# ACTUATOR_PWR_PROT.net
KiCad netlist of a schematic drawn in Altium Designer
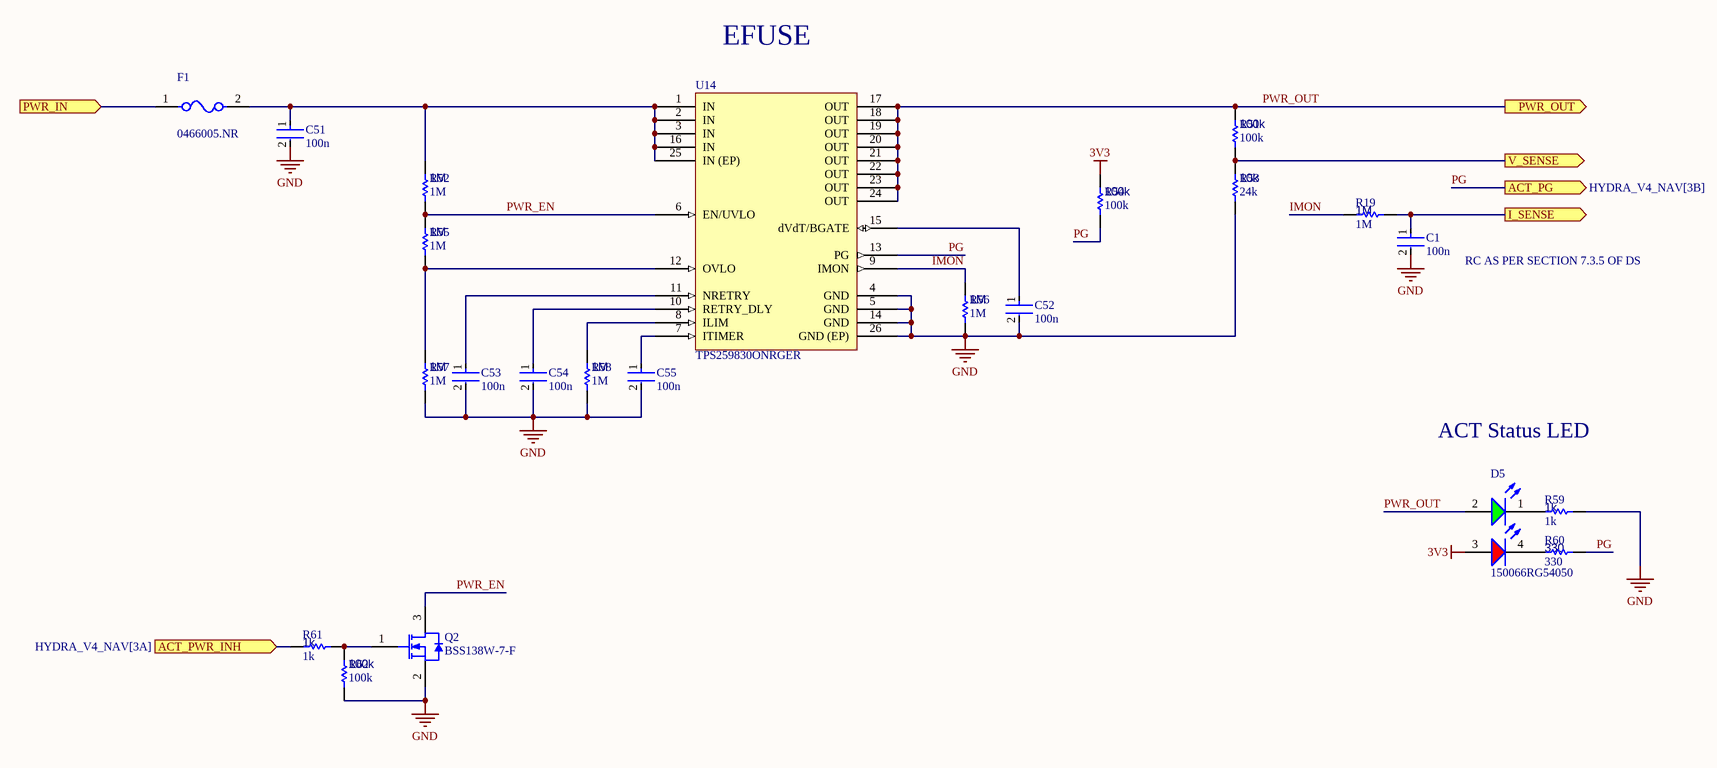
[diagram p0: ACTUATOR_PWR_PROT.SchDoc]

(export (version "E")
  (design (tool "Eeschema 10.0.6"))
  (components
    (comp (ref "C1")
      (value "100n")
      (footprint "FP-0402-L_1_0_0_05-W_0_5-IPC_A")
      (description "LARGE PADS, 0402 CAP, CHANGE COMMENT TO MATCH REAL P/N")
      (libsource (lib "Space Concordia") (part "b4654b650e69147ec39a6b967a45e02"))
    )
    (comp (ref "C51")
      (value "100n")
      (footprint "FP-0402-L_1_0_0_05-W_0_5-IPC_A")
      (description "LARGE PADS, 0402 CAP, CHANGE COMMENT TO MATCH REAL P/N")
      (libsource (lib "Space Concordia") (part "b4654b650e69147ec39a6b967a45e02"))
    )
    (comp (ref "C52")
      (value "100n")
      (footprint "FP-0402-L_1_0_0_05-W_0_5-IPC_A")
      (description "LARGE PADS, 0402 CAP, CHANGE COMMENT TO MATCH REAL P/N")
      (libsource (lib "Space Concordia") (part "b4654b650e69147ec39a6b967a45e02"))
    )
    (comp (ref "C53")
      (value "100n")
      (footprint "FP-0402-L_1_0_0_05-W_0_5-IPC_A")
      (description "LARGE PADS, 0402 CAP, CHANGE COMMENT TO MATCH REAL P/N")
      (libsource (lib "Space Concordia") (part "b4654b650e69147ec39a6b967a45e02"))
    )
    (comp (ref "C54")
      (value "100n")
      (footprint "FP-0402-L_1_0_0_05-W_0_5-IPC_A")
      (description "LARGE PADS, 0402 CAP, CHANGE COMMENT TO MATCH REAL P/N")
      (libsource (lib "Space Concordia") (part "b4654b650e69147ec39a6b967a45e02"))
    )
    (comp (ref "C55")
      (value "100n")
      (footprint "FP-0402-L_1_0_0_05-W_0_5-IPC_A")
      (description "LARGE PADS, 0402 CAP, CHANGE COMMENT TO MATCH REAL P/N")
      (libsource (lib "Space Concordia") (part "b4654b650e69147ec39a6b967a45e02"))
    )
    (comp (ref "D5")
      (value "150066RG54050")
      (footprint "WL-SBCD_0606")
      (description "Led, Red/Grn, 180Mcd/230Mcd, 624Nm/525Nm Rohs Compliant: Yes")
      (fields (field (name "SOURCE") "rgled.SchLib"))
      (libsource (lib "Space Concordia") (part "CMP-004-00034-2"))
    )
    (comp (ref "F1")
      (value "0466005.NR")
      (footprint "FP-0466-MFG")
      (description "FUSE BOARD MNT 5A 32VAC/VDC 1206")
      (fields
        (field (name "OCTOPART") "https://octopart.com/0466005.nr-littelfuse-143206")
        (field (name "MANUFACTURER") "Littelfuse Inc")
      )
      (libsource (lib "Altium Content Vault") (part "5bcf9b9f640e542cf0359d10258e979"))
    )
    (comp (ref "Q2")
      (value "BSS138W-7-F")
      (footprint "DIOD-SOT323-3_V")
      (fields (field (name "MANUFACTURER") "DiodesIncorporated"))
      (libsource (lib "Altium Content Vault") (part "NEMOS-GSD-3"))
    )
    (comp (ref "R19")
      (value "1M")
      (footprint "R0603B")
      (description "Resistor")
      (fields (field (name "ALTIUM_VALUE") "1M"))
      (libsource (lib "Space Concordia") (part "Resistor"))
    )
    (comp (ref "R51")
      (value "100k")
      (footprint "R0603B")
      (description "Resistor")
      (fields (field (name "ALTIUM_VALUE") "100k"))
      (libsource (lib "Space Concordia") (part "Resistor"))
    )
    (comp (ref "R52")
      (value "1M")
      (footprint "R0603B")
      (description "Resistor")
      (fields (field (name "ALTIUM_VALUE") "1M"))
      (libsource (lib "Space Concordia") (part "Resistor"))
    )
    (comp (ref "R53")
      (value "24k")
      (footprint "R0603B")
      (description "Resistor")
      (fields (field (name "ALTIUM_VALUE") "10k"))
      (libsource (lib "Space Concordia") (part "Resistor"))
    )
    (comp (ref "R54")
      (value "100k")
      (footprint "R0603B")
      (description "Resistor")
      (fields (field (name "ALTIUM_VALUE") "100k"))
      (libsource (lib "Space Concordia") (part "Resistor"))
    )
    (comp (ref "R55")
      (value "1M")
      (footprint "R0603B")
      (description "Resistor")
      (fields (field (name "ALTIUM_VALUE") "1M"))
      (libsource (lib "Space Concordia") (part "Resistor"))
    )
    (comp (ref "R56")
      (value "1M")
      (footprint "R0603B")
      (description "Resistor")
      (fields (field (name "ALTIUM_VALUE") "1M"))
      (libsource (lib "Space Concordia") (part "Resistor"))
    )
    (comp (ref "R57")
      (value "1M")
      (footprint "R0603B")
      (description "Resistor")
      (fields (field (name "ALTIUM_VALUE") "1M"))
      (libsource (lib "Space Concordia") (part "Resistor"))
    )
    (comp (ref "R58")
      (value "1M")
      (footprint "R0603B")
      (description "Resistor")
      (fields (field (name "ALTIUM_VALUE") "1M"))
      (libsource (lib "Space Concordia") (part "Resistor"))
    )
    (comp (ref "R59")
      (value "1k")
      (footprint "R0603B")
      (description "Resistor")
      (fields (field (name "ALTIUM_VALUE") "1k"))
      (libsource (lib "Space Concordia") (part "Resistor"))
    )
    (comp (ref "R60")
      (value "330")
      (footprint "R0603B")
      (description "Resistor")
      (fields (field (name "ALTIUM_VALUE") "330"))
      (libsource (lib "Space Concordia") (part "Resistor"))
    )
    (comp (ref "R61")
      (value "1k")
      (footprint "R0603B")
      (description "Resistor")
      (fields (field (name "ALTIUM_VALUE") "1k"))
      (libsource (lib "Space Concordia") (part "Resistor"))
    )
    (comp (ref "R62")
      (value "100k")
      (footprint "R0603B")
      (description "Resistor")
      (fields (field (name "ALTIUM_VALUE") "100k"))
      (libsource (lib "Space Concordia") (part "Resistor"))
    )
    (comp (ref "U14")
      (value "TPS259830ONRGER")
      (footprint "QFN50P400X400X100_HS-25N")
      (libsource (lib "Space Concordia") (part "TPS259830ONRGER"))
    )
  )
  (nets
    (net (code "1") (name "/ACT_PWR_INH") (class "Default")
      (node (ref "R61") (pin "1") (pinfunction "1_1") (pintype "passive"))
    )
    (net (code "2") (name "/IMON") (class "Default")
      (node (ref "R19") (pin "1") (pinfunction "1_1") (pintype "passive"))
      (node (ref "R56") (pin "1") (pinfunction "1_1") (pintype "passive"))
      (node (ref "U14") (pin "9") (pinfunction "IMON_9") (pintype "output"))
    )
    (net (code "3") (name "/I_SENSE") (class "Default")
      (node (ref "C1") (pin "1") (pinfunction "1_1") (pintype "passive"))
      (node (ref "R19") (pin "2") (pinfunction "2_2") (pintype "passive"))
    )
    (net (code "4") (name "/PG") (class "Default")
      (node (ref "R54") (pin "2") (pinfunction "2_2") (pintype "passive"))
      (node (ref "R60") (pin "2") (pinfunction "2_2") (pintype "passive"))
      (node (ref "U14") (pin "13") (pinfunction "PG_13") (pintype "output"))
    )
    (net (code "5") (name "/PWR_EN") (class "Default")
      (node (ref "Q2") (pin "3") (pinfunction "D_3") (pintype "passive"))
      (node (ref "R52") (pin "2") (pinfunction "2_2") (pintype "passive"))
      (node (ref "R55") (pin "1") (pinfunction "1_1") (pintype "passive"))
      (node (ref "U14") (pin "6") (pinfunction "EN/UVLO_6") (pintype "input"))
    )
    (net (code "6") (name "/PWR_IN") (class "Default")
      (node (ref "F1") (pin "1") (pinfunction "1_1") (pintype "passive"))
    )
    (net (code "7") (name "/PWR_OUT") (class "Default")
      (node (ref "D5") (pin "2") (pinfunction "A_2") (pintype "passive"))
      (node (ref "R51") (pin "1") (pinfunction "1_1") (pintype "passive"))
      (node (ref "U14") (pin "17") (pinfunction "OUT_17") (pintype "power_in"))
      (node (ref "U14") (pin "18") (pinfunction "OUT_18") (pintype "power_in"))
      (node (ref "U14") (pin "19") (pinfunction "OUT_19") (pintype "power_in"))
      (node (ref "U14") (pin "20") (pinfunction "OUT_20") (pintype "power_in"))
      (node (ref "U14") (pin "21") (pinfunction "OUT_21") (pintype "power_in"))
      (node (ref "U14") (pin "22") (pinfunction "OUT_22") (pintype "power_in"))
      (node (ref "U14") (pin "23") (pinfunction "OUT_23") (pintype "power_in"))
      (node (ref "U14") (pin "24") (pinfunction "OUT_24") (pintype "power_in"))
    )
    (net (code "8") (name "/V_SENSE") (class "Default")
      (node (ref "R51") (pin "2") (pinfunction "2_2") (pintype "passive"))
      (node (ref "R53") (pin "1") (pinfunction "1_1") (pintype "passive"))
    )
    (net (code "9") (name "3V3") (class "Default")
      (node (ref "D5") (pin "3") (pinfunction "A_3") (pintype "passive"))
      (node (ref "R54") (pin "1") (pinfunction "1_1") (pintype "passive"))
    )
    (net (code "10") (name "GND") (class "Default")
      (node (ref "C1") (pin "2") (pinfunction "2_2") (pintype "passive"))
      (node (ref "C51") (pin "2") (pinfunction "2_2") (pintype "passive"))
      (node (ref "C52") (pin "2") (pinfunction "2_2") (pintype "passive"))
      (node (ref "C53") (pin "2") (pinfunction "2_2") (pintype "passive"))
      (node (ref "C54") (pin "2") (pinfunction "2_2") (pintype "passive"))
      (node (ref "C55") (pin "2") (pinfunction "2_2") (pintype "passive"))
      (node (ref "Q2") (pin "2") (pinfunction "S_2") (pintype "passive"))
      (node (ref "R53") (pin "2") (pinfunction "2_2") (pintype "passive"))
      (node (ref "R56") (pin "2") (pinfunction "2_2") (pintype "passive"))
      (node (ref "R57") (pin "2") (pinfunction "2_2") (pintype "passive"))
      (node (ref "R58") (pin "2") (pinfunction "2_2") (pintype "passive"))
      (node (ref "R59") (pin "2") (pinfunction "2_2") (pintype "passive"))
      (node (ref "R62") (pin "2") (pinfunction "2_2") (pintype "passive"))
      (node (ref "U14") (pin "14") (pinfunction "GND_14") (pintype "power_in"))
      (node (ref "U14") (pin "26") (pinfunction "GND_(EP)_26") (pintype "power_in"))
      (node (ref "U14") (pin "4") (pinfunction "GND_4") (pintype "power_in"))
      (node (ref "U14") (pin "5") (pinfunction "GND_5") (pintype "power_in"))
    )
    (net (code "11") (name "Net-(D5-K-Pad1)") (class "Default")
      (node (ref "D5") (pin "1") (pinfunction "K_1") (pintype "passive"))
      (node (ref "R59") (pin "1") (pinfunction "1_1") (pintype "passive"))
    )
    (net (code "12") (name "Net-(D5-K-Pad4)") (class "Default")
      (node (ref "D5") (pin "4") (pinfunction "K_4") (pintype "passive"))
      (node (ref "R60") (pin "1") (pinfunction "1_1") (pintype "passive"))
    )
    (net (code "13") (name "Net-(Q2-G)") (class "Default")
      (node (ref "Q2") (pin "1") (pinfunction "G_1") (pintype "passive"))
      (node (ref "R61") (pin "2") (pinfunction "2_2") (pintype "passive"))
      (node (ref "R62") (pin "1") (pinfunction "1_1") (pintype "passive"))
    )
    (net (code "14") (name "Net-(U14-ILIM)") (class "Default")
      (node (ref "R58") (pin "1") (pinfunction "1_1") (pintype "passive"))
      (node (ref "U14") (pin "8") (pinfunction "ILIM_8") (pintype "input"))
    )
    (net (code "15") (name "Net-(U14-IN_(EP))") (class "Default")
      (node (ref "C51") (pin "1") (pinfunction "1_1") (pintype "passive"))
      (node (ref "F1") (pin "2") (pinfunction "2_2") (pintype "passive"))
      (node (ref "R52") (pin "1") (pinfunction "1_1") (pintype "passive"))
      (node (ref "U14") (pin "1") (pinfunction "IN_1") (pintype "power_in"))
      (node (ref "U14") (pin "16") (pinfunction "IN_16") (pintype "power_in"))
      (node (ref "U14") (pin "2") (pinfunction "IN_2") (pintype "power_in"))
      (node (ref "U14") (pin "25") (pinfunction "IN_(EP)_25") (pintype "power_in"))
      (node (ref "U14") (pin "3") (pinfunction "IN_3") (pintype "power_in"))
    )
    (net (code "16") (name "Net-(U14-ITIMER)") (class "Default")
      (node (ref "C55") (pin "1") (pinfunction "1_1") (pintype "passive"))
      (node (ref "U14") (pin "7") (pinfunction "ITIMER_7") (pintype "input"))
    )
    (net (code "17") (name "Net-(U14-NRETRY)") (class "Default")
      (node (ref "C53") (pin "1") (pinfunction "1_1") (pintype "passive"))
      (node (ref "U14") (pin "11") (pinfunction "NRETRY_11") (pintype "input"))
    )
    (net (code "18") (name "Net-(U14-OVLO)") (class "Default")
      (node (ref "R55") (pin "2") (pinfunction "2_2") (pintype "passive"))
      (node (ref "R57") (pin "1") (pinfunction "1_1") (pintype "passive"))
      (node (ref "U14") (pin "12") (pinfunction "OVLO_12") (pintype "input"))
    )
    (net (code "19") (name "Net-(U14-RETRY_DLY)") (class "Default")
      (node (ref "C54") (pin "1") (pinfunction "1_1") (pintype "passive"))
      (node (ref "U14") (pin "10") (pinfunction "RETRY_DLY_10") (pintype "input"))
    )
    (net (code "20") (name "Net-(U14-dVdT{slash}BGATE)") (class "Default")
      (node (ref "C52") (pin "1") (pinfunction "1_1") (pintype "passive"))
      (node (ref "U14") (pin "15") (pinfunction "dVdT/BGATE_15") (pintype "bidirectional"))
    )
  )
)
